# drvoutput5.net
KiCad netlist of a schematic drawn in Altium Designer
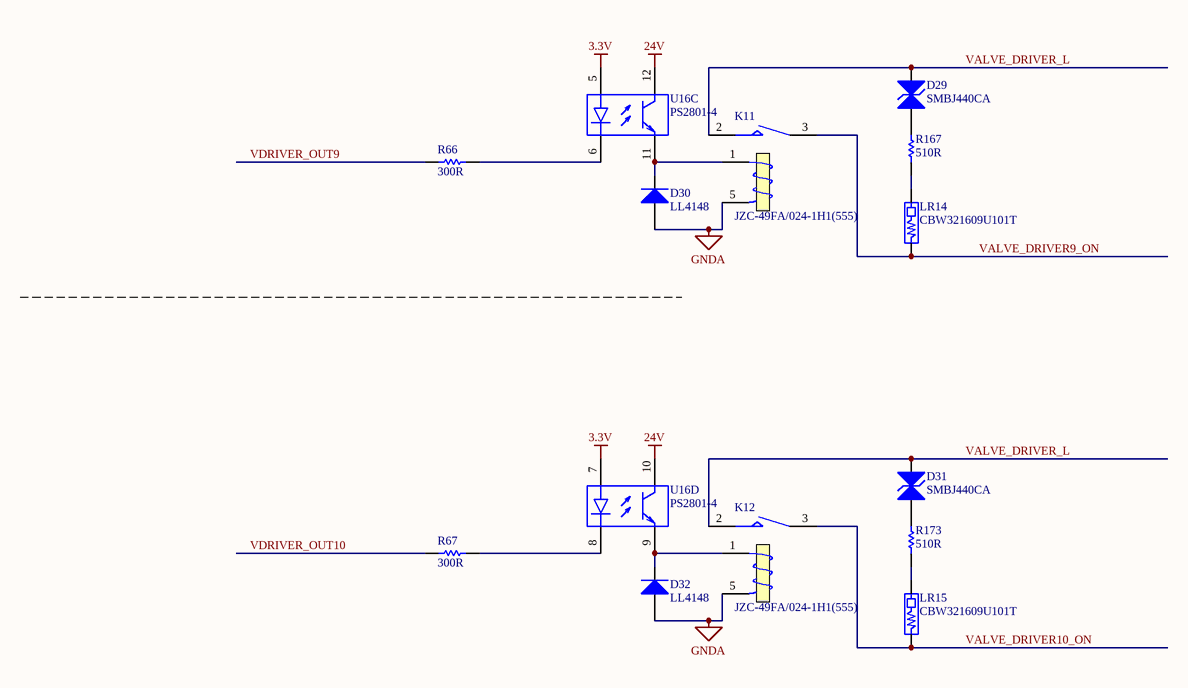
[diagram p0: drvoutput5.SchDoc]

(export (version "E")
  (design (tool "Eeschema 10.0.6"))
  (components
    (comp (ref "D29")
      (value "SMBJ440CA")
      (footprint "SMB")
      (description "Bi-dir TVS Diode")
      (fields (field (name "PUBLISHER") "Altium Limited"))
      (libsource (lib "UserLib") (part "Bi-dir TVS Diode"))
    )
    (comp (ref "D30")
      (value "LL4148")
      (footprint "CD2012-0805")
      (description "1 Amp General Purpose Rectifier")
      (fields (field (name "PUBLISHER") "Altium Limited"))
      (libsource (lib "Miscellaneous Devices") (part "Diode 1N4007"))
    )
    (comp (ref "D31")
      (value "SMBJ440CA")
      (footprint "SMB")
      (description "Bi-dir TVS Diode")
      (fields (field (name "PUBLISHER") "Altium Limited"))
      (libsource (lib "UserLib") (part "Bi-dir TVS Diode"))
    )
    (comp (ref "D32")
      (value "LL4148")
      (footprint "CD2012-0805")
      (description "1 Amp General Purpose Rectifier")
      (fields (field (name "PUBLISHER") "Altium Limited"))
      (libsource (lib "Miscellaneous Devices") (part "Diode 1N4007"))
    )
    (comp (ref "K11")
      (value "JZC-49FA/024-1H1(555)")
      (footprint "JZC-49FA")
      (description "Intermediate  Power  Relay")
      (fields (field (name "PUBLISHER") "Altium Limited"))
      (libsource (lib "UserSchDev") (part "JZC-49FA"))
    )
    (comp (ref "K12")
      (value "JZC-49FA/024-1H1(555)")
      (footprint "JZC-49FA")
      (description "Intermediate  Power  Relay")
      (fields (field (name "PUBLISHER") "Altium Limited"))
      (libsource (lib "UserSchDev") (part "JZC-49FA"))
    )
    (comp (ref "LR14")
      (value "CBW321609U101T")
      (footprint "INDC3216M")
      (description "EMI FILTERS,DC Resistance max.0.05~1.5 ohms,10 ~ 1000 ohms at 100MHz  Frequency")
      (libsource (lib "UserLib") (part "BLM10/11/21/31/41"))
    )
    (comp (ref "LR15")
      (value "CBW321609U101T")
      (footprint "INDC3216M")
      (description "EMI FILTERS,DC Resistance max.0.05~1.5 ohms,10 ~ 1000 ohms at 100MHz  Frequency")
      (libsource (lib "UserLib") (part "BLM10/11/21/31/41"))
    )
    (comp (ref "R66")
      (value "300R")
      (footprint "RESC2012M")
      (description "Resistor")
      (fields (field (name "PUBLISHER") "Altium Limited"))
      (libsource (lib "Miscellaneous Devices") (part "Res1"))
    )
    (comp (ref "R67")
      (value "300R")
      (footprint "RESC2012M")
      (description "Resistor")
      (fields (field (name "PUBLISHER") "Altium Limited"))
      (libsource (lib "Miscellaneous Devices") (part "Res1"))
    )
    (comp (ref "R167")
      (value "510R")
      (footprint "RESC3216M")
      (description "Metal film Resistor")
      (fields (field (name "PUBLISHER") "Altium Limited"))
      (libsource (lib "Miscellaneous Devices") (part "Res1"))
    )
    (comp (ref "R173")
      (value "510R")
      (footprint "RESC3216M")
      (description "Metal film Resistor")
      (fields (field (name "PUBLISHER") "Altium Limited"))
      (libsource (lib "Miscellaneous Devices") (part "Res1"))
    )
    (comp (ref "U16")
      (value "PS2801-4")
      (footprint "SOIC16_N")
      (fields (field (name "PUBLISHER") "Altium Limited"))
      (libsource (lib "UserSchDev") (part "PS2801-4"))
    )
  )
  (nets
    (net (code "1") (name "/VALVE_DRIVER9_ON") (class "Default")
      (node (ref "K11") (pin "3") (pinfunction "NO_3") (pintype "passive"))
      (node (ref "LR14") (pin "1") (pinfunction "1_1") (pintype "passive"))
    )
    (net (code "2") (name "/VALVE_DRIVER10_ON") (class "Default")
      (node (ref "K12") (pin "3") (pinfunction "NO_3") (pintype "passive"))
      (node (ref "LR15") (pin "1") (pinfunction "1_1") (pintype "passive"))
    )
    (net (code "3") (name "/VALVE_DRIVER_L") (class "Default")
      (node (ref "D29") (pin "2") (pinfunction "K_2") (pintype "passive"))
      (node (ref "D31") (pin "2") (pinfunction "K_2") (pintype "passive"))
      (node (ref "K11") (pin "2") (pinfunction "COM_2") (pintype "passive"))
      (node (ref "K12") (pin "2") (pinfunction "COM_2") (pintype "passive"))
    )
    (net (code "4") (name "/VDRIVER_OUT9") (class "Default")
      (node (ref "R66") (pin "1") (pinfunction "1_1") (pintype "passive"))
    )
    (net (code "5") (name "/VDRIVER_OUT10") (class "Default")
      (node (ref "R67") (pin "1") (pinfunction "1_1") (pintype "passive"))
    )
    (net (code "6") (name "3.3V") (class "Default")
      (node (ref "U16") (pin "5") (pinfunction "+_5") (pintype "passive"))
      (node (ref "U16") (pin "7") (pinfunction "+_7") (pintype "passive"))
    )
    (net (code "7") (name "24V") (class "Default")
      (node (ref "U16") (pin "10") (pinfunction "C_10") (pintype "passive"))
      (node (ref "U16") (pin "12") (pinfunction "C_12") (pintype "passive"))
    )
    (net (code "8") (name "GNDA") (class "Default")
      (node (ref "D30") (pin "1") (pinfunction "A_1") (pintype "passive"))
      (node (ref "D32") (pin "1") (pinfunction "A_1") (pintype "passive"))
      (node (ref "K11") (pin "5") (pinfunction "T2_5") (pintype "passive"))
      (node (ref "K12") (pin "5") (pinfunction "T2_5") (pintype "passive"))
    )
    (net (code "9") (name "Net-(D29-A)") (class "Default")
      (node (ref "D29") (pin "1") (pinfunction "A_1") (pintype "passive"))
      (node (ref "R167") (pin "2") (pinfunction "2_2") (pintype "passive"))
    )
    (net (code "10") (name "Net-(D30-K)") (class "Default")
      (node (ref "D30") (pin "2") (pinfunction "K_2") (pintype "passive"))
      (node (ref "K11") (pin "1") (pinfunction "1_1") (pintype "passive"))
      (node (ref "U16") (pin "11") (pinfunction "E_11") (pintype "passive"))
    )
    (net (code "11") (name "Net-(D31-A)") (class "Default")
      (node (ref "D31") (pin "1") (pinfunction "A_1") (pintype "passive"))
      (node (ref "R173") (pin "2") (pinfunction "2_2") (pintype "passive"))
    )
    (net (code "12") (name "Net-(D32-K)") (class "Default")
      (node (ref "D32") (pin "2") (pinfunction "K_2") (pintype "passive"))
      (node (ref "K12") (pin "1") (pinfunction "1_1") (pintype "passive"))
      (node (ref "U16") (pin "9") (pinfunction "E_9") (pintype "passive"))
    )
    (net (code "13") (name "Net-(LR14-Pad2)") (class "Default")
      (node (ref "LR14") (pin "2") (pinfunction "2_2") (pintype "passive"))
      (node (ref "R167") (pin "1") (pinfunction "1_1") (pintype "passive"))
    )
    (net (code "14") (name "Net-(LR15-Pad2)") (class "Default")
      (node (ref "LR15") (pin "2") (pinfunction "2_2") (pintype "passive"))
      (node (ref "R173") (pin "1") (pinfunction "1_1") (pintype "passive"))
    )
    (net (code "15") (name "Net-(U16C--)") (class "Default")
      (node (ref "R66") (pin "2") (pinfunction "2_2") (pintype "passive"))
      (node (ref "U16") (pin "6") (pinfunction "-_6") (pintype "passive"))
    )
    (net (code "16") (name "Net-(U16D--)") (class "Default")
      (node (ref "R67") (pin "2") (pinfunction "2_2") (pintype "passive"))
      (node (ref "U16") (pin "8") (pinfunction "-_8") (pintype "passive"))
    )
  )
)
